# audio.net
KiCad netlist of a schematic drawn in Altium Designer
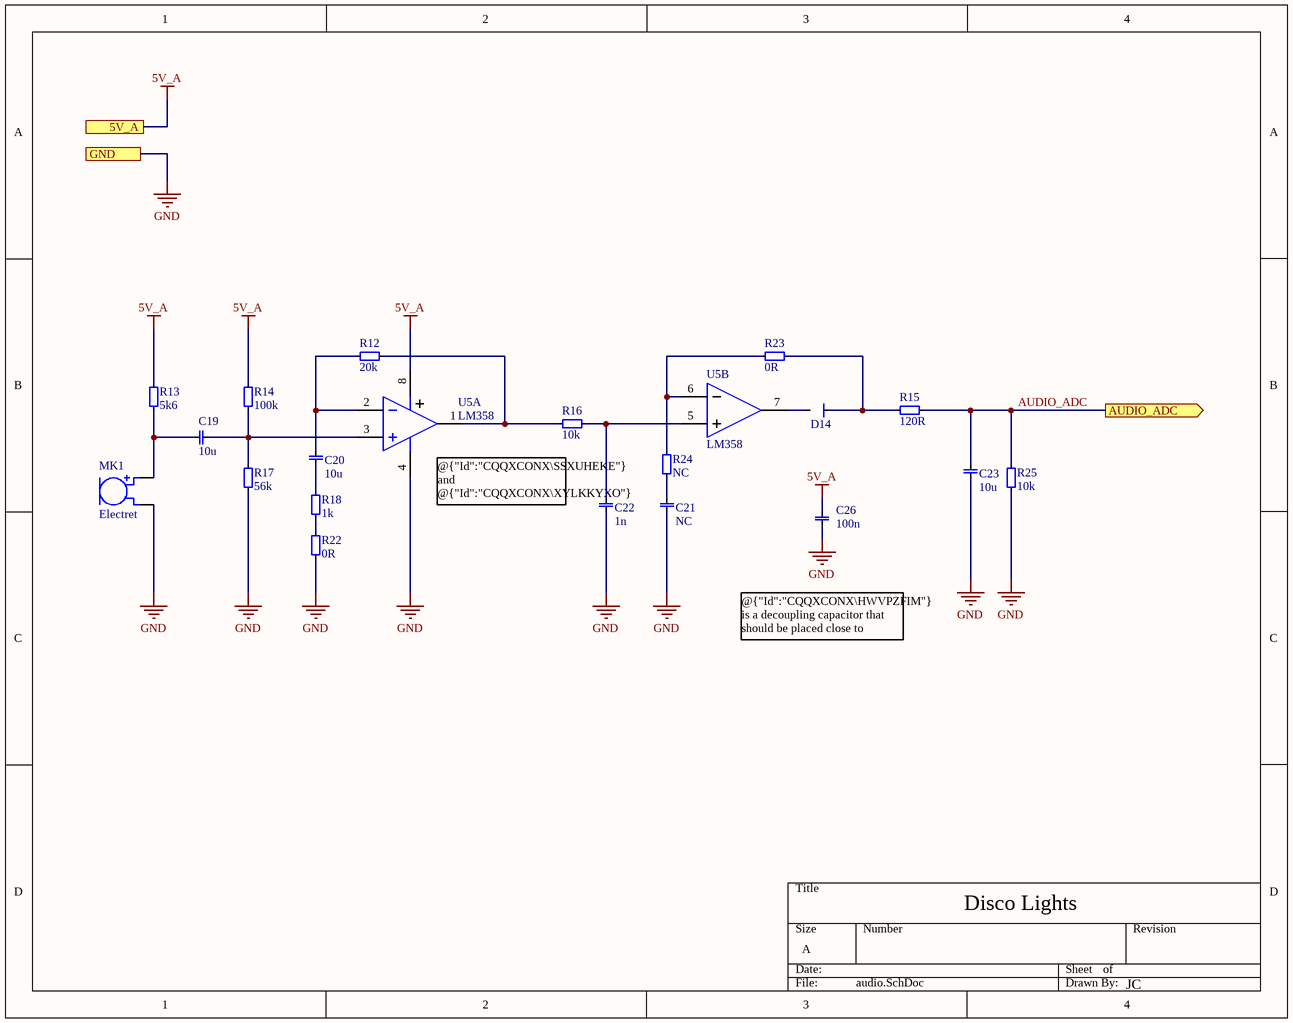
[diagram p0: audio.SchDoc]

(export (version "E")
  (design (tool "Eeschema 10.0.6"))
  (components
    (comp (ref "C19")
      (value "10u")
      (footprint "0603 cap")
      (fields
        (field (name "JLCPCB PART #") "C386081")
        (field (name "MANUFACTURER PART NUMBER") "TMK107BBJ106MA-T")
        (field (name "Comment") "0603, capacitor")
      )
      (libsource (lib "jclib") (part "0603, capacitor"))
    )
    (comp (ref "C20")
      (value "10u")
      (footprint "0603 cap")
      (fields
        (field (name "JLCPCB PART #") "C386081")
        (field (name "MANUFACTURER PART NUMBER") "TMK107BBJ106MA-T")
        (field (name "Comment") "0603, capacitor")
      )
      (libsource (lib "jclib") (part "0603, capacitor"))
    )
    (comp (ref "C21")
      (value "NC")
      (footprint "0603 cap")
      (fields (field (name "Comment") "0603, capacitor"))
      (libsource (lib "jclib") (part "0603, capacitor"))
    )
    (comp (ref "C22")
      (value "1n")
      (footprint "0603 cap")
      (fields
        (field (name "JLCPCB PART #") "C100040")
        (field (name "MANUFACTURER PART NUMBER") "CC0603KRX7R9BB102")
        (field (name "Comment") "0603, capacitor")
      )
      (libsource (lib "jclib") (part "0603, capacitor"))
    )
    (comp (ref "C23")
      (value "10u")
      (footprint "0603 cap")
      (fields
        (field (name "JLCPCB PART #") "C386081")
        (field (name "MANUFACTURER PART NUMBER") "TMK107BBJ106MA-T")
        (field (name "Comment") "0603, capacitor")
      )
      (libsource (lib "jclib") (part "0603, capacitor"))
    )
    (comp (ref "C26")
      (value "100n")
      (footprint "0603 cap")
      (fields
        (field (name "JLCPCB PART #") "C14663")
        (field (name "MANUFACTURER PART NUMBER") "CC0603KRX7R9BB102")
        (field (name "Comment") "0603, capacitor")
      )
      (libsource (lib "jclib") (part "0603, capacitor"))
    )
    (comp (ref "D14")
      (value "Diode, SMD")
      (footprint "SOD323")
      (fields (field (name "JLCPCB PART #") "C117941") (field (name "MANUFACTURER PART NUMBER") "BAT760,115"))
      (libsource (lib "jclib") (part "Diode, SMD"))
    )
    (comp (ref "MK1")
      (value "Electret")
      (footprint "ElectretMic_9.7mm_6.7mm")
      (description "D9.7mm H6.7mm, Electrokit art nr: 40290007")
      (libsource (lib "jclib") (part "Electret Mic"))
    )
    (comp (ref "R12")
      (value "20k")
      (footprint "0603")
      (fields
        (field (name "JLCPCB PART #") "C723637")
        (field (name "MANUFACTURER PART NUMBER") "RT0603BRD0720KL")
        (field (name "Comment") "0603, resistor")
      )
      (libsource (lib "jclib") (part "0603, resistor"))
    )
    (comp (ref "R13")
      (value "5k6")
      (footprint "0603")
      (fields
        (field (name "JLCPCB PART #") "C138278")
        (field (name "MANUFACTURER PART NUMBER") "AC0603FR-075K6L")
        (field (name "Comment") "0603, resistor")
      )
      (libsource (lib "jclib") (part "0603, resistor"))
    )
    (comp (ref "R14")
      (value "100k")
      (footprint "0603")
      (fields
        (field (name "JLCPCB PART #") "C14675")
        (field (name "MANUFACTURER PART NUMBER") "RC0603FR-07100KL")
        (field (name "Comment") "0603, resistor")
      )
      (libsource (lib "jclib") (part "0603, resistor"))
    )
    (comp (ref "R15")
      (value "120R")
      (footprint "0603")
      (fields
        (field (name "JLCPCB PART #") "C114681")
        (field (name "MANUFACTURER PART NUMBER") "RC0603JR-07120RL")
        (field (name "Comment") "0603, resistor")
      )
      (libsource (lib "jclib") (part "0603, resistor"))
    )
    (comp (ref "R16")
      (value "10k")
      (footprint "0603")
      (fields
        (field (name "JLCPCB PART #") "C98220")
        (field (name "MANUFACTURER PART NUMBER") "RC0603FR-0710KL")
        (field (name "Comment") "0603, resistor")
      )
      (libsource (lib "jclib") (part "0603, resistor"))
    )
    (comp (ref "R17")
      (value "56k")
      (footprint "0603")
      (fields
        (field (name "JLCPCB PART #") "C114630")
        (field (name "MANUFACTURER PART NUMBER") "C3216X7R1C106KT000N")
        (field (name "Comment") "0603, resistor")
      )
      (libsource (lib "jclib") (part "0603, resistor"))
    )
    (comp (ref "R18")
      (value "1k")
      (footprint "0603")
      (fields
        (field (name "JLCPCB PART #") "C21190")
        (field (name "MANUFACTURER PART NUMBER") "CR0603-FX-1001ELF")
        (field (name "Comment") "0603, resistor")
      )
      (libsource (lib "jclib") (part "0603, resistor"))
    )
    (comp (ref "R22")
      (value "0R")
      (footprint "0603")
      (fields
        (field (name "JLCPCB PART #") "C95177")
        (field (name "MANUFACTURER PART NUMBER") "RC0603JR-070RL")
        (field (name "Comment") "0603, resistor")
      )
      (libsource (lib "jclib") (part "0603, resistor"))
    )
    (comp (ref "R23")
      (value "0R")
      (footprint "0603")
      (fields
        (field (name "JLCPCB PART #") "C95177")
        (field (name "MANUFACTURER PART NUMBER") "RC0603JR-070RL")
        (field (name "Comment") "0603, resistor")
      )
      (libsource (lib "jclib") (part "0603, resistor"))
    )
    (comp (ref "R24")
      (value "NC")
      (footprint "0603")
      (fields (field (name "Comment") "0603, resistor"))
      (libsource (lib "jclib") (part "0603, resistor"))
    )
    (comp (ref "R25")
      (value "10k")
      (footprint "0603")
      (fields
        (field (name "JLCPCB PART #") "C98220")
        (field (name "MANUFACTURER PART NUMBER") "RC0603FR-0710KL")
        (field (name "Comment") "0603, resistor")
      )
      (libsource (lib "jclib") (part "0603, resistor"))
    )
    (comp (ref "U5")
      (value "LM358")
      (footprint "SOIC8")
      (description "Dual FET-Input Operational Amplifier")
      (libsource (lib "jclib") (part "LM358"))
    )
  )
  (nets
    (net (code "1") (name "/AUDIO_ADC") (class "Default")
      (node (ref "C23") (pin "0") (pinfunction "0_0") (pintype "passive"))
      (node (ref "R15") (pin "1") (pinfunction "1_1") (pintype "passive"))
      (node (ref "R25") (pin "0") (pinfunction "0_0") (pintype "passive"))
    )
    (net (code "2") (name "5V_A") (class "Default")
      (node (ref "C26") (pin "1") (pinfunction "1_1") (pintype "passive"))
      (node (ref "R13") (pin "0") (pinfunction "0_0") (pintype "passive"))
      (node (ref "R14") (pin "0") (pinfunction "0_0") (pintype "passive"))
      (node (ref "U5") (pin "8") (pinfunction "V+_8") (pintype "power_in"))
    )
    (net (code "3") (name "GND") (class "Default")
      (node (ref "C21") (pin "0") (pinfunction "0_0") (pintype "passive"))
      (node (ref "C22") (pin "0") (pinfunction "0_0") (pintype "passive"))
      (node (ref "C23") (pin "1") (pinfunction "1_1") (pintype "passive"))
      (node (ref "C26") (pin "0") (pinfunction "0_0") (pintype "passive"))
      (node (ref "MK1") (pin "2") (pinfunction "2_2") (pintype "passive"))
      (node (ref "R17") (pin "1") (pinfunction "1_1") (pintype "passive"))
      (node (ref "R22") (pin "0") (pinfunction "0_0") (pintype "passive"))
      (node (ref "R25") (pin "1") (pinfunction "1_1") (pintype "passive"))
      (node (ref "U5") (pin "4") (pinfunction "V-_4") (pintype "power_in"))
    )
    (net (code "4") (name "Net-(C19-Pad1)") (class "Default")
      (node (ref "C19") (pin "1") (pinfunction "1_1") (pintype "passive"))
      (node (ref "MK1") (pin "1") (pinfunction "1_1") (pintype "passive"))
      (node (ref "R13") (pin "1") (pinfunction "1_1") (pintype "passive"))
    )
    (net (code "5") (name "Net-(C20-Pad0)") (class "Default")
      (node (ref "C20") (pin "0") (pinfunction "0_0") (pintype "passive"))
      (node (ref "R18") (pin "0") (pinfunction "0_0") (pintype "passive"))
    )
    (net (code "6") (name "Net-(C21-Pad1)") (class "Default")
      (node (ref "C21") (pin "1") (pinfunction "1_1") (pintype "passive"))
      (node (ref "R24") (pin "1") (pinfunction "1_1") (pintype "passive"))
    )
    (net (code "7") (name "Net-(D14-Pad1)") (class "Default")
      (node (ref "D14") (pin "1") (pinfunction "1_1") (pintype "passive"))
      (node (ref "R15") (pin "0") (pinfunction "0_0") (pintype "passive"))
      (node (ref "R23") (pin "1") (pinfunction "1_1") (pintype "passive"))
    )
    (net (code "8") (name "Net-(R18-Pad1)") (class "Default")
      (node (ref "R18") (pin "1") (pinfunction "1_1") (pintype "passive"))
      (node (ref "R22") (pin "1") (pinfunction "1_1") (pintype "passive"))
    )
    (net (code "9") (name "Net-(U5A-IN+)") (class "Default")
      (node (ref "C19") (pin "0") (pinfunction "0_0") (pintype "passive"))
      (node (ref "R14") (pin "1") (pinfunction "1_1") (pintype "passive"))
      (node (ref "R17") (pin "0") (pinfunction "0_0") (pintype "passive"))
      (node (ref "U5") (pin "3") (pinfunction "IN+_3") (pintype "passive"))
    )
    (net (code "10") (name "Net-(U5A-IN-)") (class "Default")
      (node (ref "C20") (pin "1") (pinfunction "1_1") (pintype "passive"))
      (node (ref "R12") (pin "0") (pinfunction "0_0") (pintype "passive"))
      (node (ref "U5") (pin "2") (pinfunction "IN-_2") (pintype "passive"))
    )
    (net (code "11") (name "Net-(U5A-OUT1)") (class "Default")
      (node (ref "R12") (pin "1") (pinfunction "1_1") (pintype "passive"))
      (node (ref "R16") (pin "0") (pinfunction "0_0") (pintype "passive"))
      (node (ref "U5") (pin "1") (pinfunction "OUT1_1") (pintype "passive"))
    )
    (net (code "12") (name "Net-(U5B-IN+)") (class "Default")
      (node (ref "C22") (pin "1") (pinfunction "1_1") (pintype "passive"))
      (node (ref "R16") (pin "1") (pinfunction "1_1") (pintype "passive"))
      (node (ref "U5") (pin "5") (pinfunction "IN+_5") (pintype "passive"))
    )
    (net (code "13") (name "Net-(U5B-IN-)") (class "Default")
      (node (ref "R23") (pin "0") (pinfunction "0_0") (pintype "passive"))
      (node (ref "R24") (pin "0") (pinfunction "0_0") (pintype "passive"))
      (node (ref "U5") (pin "6") (pinfunction "IN-_6") (pintype "passive"))
    )
    (net (code "14") (name "Net-(U5B-OUT2)") (class "Default")
      (node (ref "D14") (pin "2") (pinfunction "2_2") (pintype "passive"))
      (node (ref "U5") (pin "7") (pinfunction "OUT2_7") (pintype "passive"))
    )
  )
)
